# TinyOne.net
KiCad netlist of a schematic drawn in EAGLE
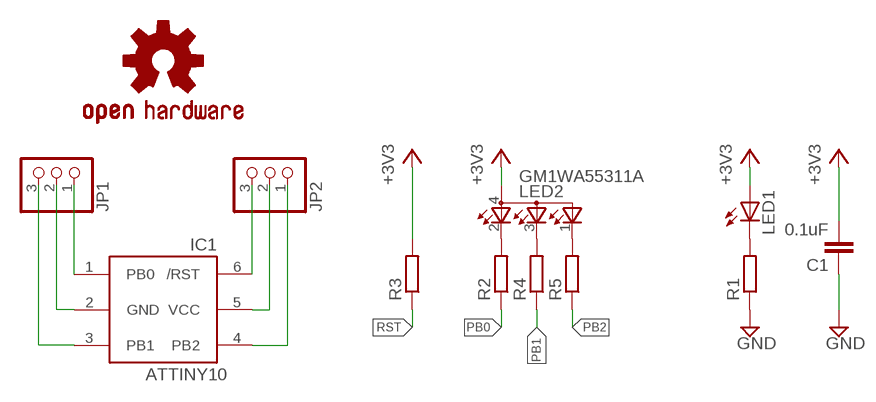
[diagram p0: schematic, sheet 1]

(export (version "E")
  (design (tool "Eeschema 10.0.6"))
  (components
    (comp (ref "C1")
      (value "0.1uF")
      (footprint "eagle-import:C0603")
      (libsource (lib "eagle-import") (part "C-EUC0603"))
    )
    (comp (ref "IC1")
      (value "ATTINY10")
      (footprint "eagle-import:SOT23-6")
      (libsource (lib "eagle-import") (part "ATTINY10"))
    )
    (comp (ref "JP1")
      (value "PINHD-1X3CB")
      (footprint "eagle-import:1X03-CLEANBIG")
      (libsource (lib "eagle-import") (part "PINHD-1X3CB"))
    )
    (comp (ref "JP2")
      (value "PINHD-1X3CB")
      (footprint "eagle-import:1X03-CLEANBIG")
      (libsource (lib "eagle-import") (part "PINHD-1X3CB"))
    )
    (comp (ref "LED1")
      (value "LEDCHIP-LED0603")
      (footprint "eagle-import:CHIP-LED0603")
      (libsource (lib "eagle-import") (part "LEDCHIP-LED0603"))
    )
    (comp (ref "LED2")
      (value "GM1WA55311A")
      (footprint "eagle-import:GM1WA55311A")
      (libsource (lib "eagle-import") (part "GM1WA55311A"))
    )
    (comp (ref "R1")
      (value "R-EU_R0603")
      (footprint "eagle-import:R0603")
      (libsource (lib "eagle-import") (part "R-EU_R0603"))
    )
    (comp (ref "R2")
      (value "R-EU_R0603")
      (footprint "eagle-import:R0603")
      (libsource (lib "eagle-import") (part "R-EU_R0603"))
    )
    (comp (ref "R3")
      (value "R-EU_R0603")
      (footprint "eagle-import:R0603")
      (libsource (lib "eagle-import") (part "R-EU_R0603"))
    )
    (comp (ref "R4")
      (value "R-EU_R0603")
      (footprint "eagle-import:R0603")
      (libsource (lib "eagle-import") (part "R-EU_R0603"))
    )
    (comp (ref "R5")
      (value "R-EU_R0603")
      (footprint "eagle-import:R0603")
      (libsource (lib "eagle-import") (part "R-EU_R0603"))
    )
    (comp (ref "U$1")
      (value "OSHW-LOGOS")
      (footprint "eagle-import:OSHW-LOGO-S")
      (libsource (lib "eagle-import") (part "OSHW-LOGOS"))
    )
  )
  (nets
    (net (code "1") (name "+3V3") (class "Default")
      (node (ref "C1") (pin "2") (pinfunction "2_2") (pintype "passive"))
      (node (ref "IC1") (pin "5") (pinfunction "VCC_5") (pintype "power_in"))
      (node (ref "JP2") (pin "2") (pinfunction "2_2") (pintype "passive"))
      (node (ref "LED1") (pin "A") (pinfunction "A_A") (pintype "passive"))
      (node (ref "LED2") (pin "4") (pinfunction "A_4") (pintype "passive"))
      (node (ref "R3") (pin "2") (pinfunction "2_2") (pintype "passive"))
    )
    (net (code "2") (name "GND") (class "Default")
      (node (ref "C1") (pin "1") (pinfunction "1_1") (pintype "passive"))
      (node (ref "IC1") (pin "2") (pinfunction "GND_2") (pintype "power_in"))
      (node (ref "JP1") (pin "2") (pinfunction "2_2") (pintype "passive"))
      (node (ref "R1") (pin "1") (pinfunction "1_1") (pintype "passive"))
    )
    (net (code "3") (name "Net-(LED1-PadC)") (class "Default")
      (node (ref "LED1") (pin "C") (pinfunction "C_C") (pintype "passive"))
      (node (ref "R1") (pin "2") (pinfunction "2_2") (pintype "passive"))
    )
    (net (code "4") (name "Net-(LED2-CBLUE)") (class "Default")
      (node (ref "LED2") (pin "3") (pinfunction "CBLUE_3") (pintype "passive"))
      (node (ref "R4") (pin "2") (pinfunction "2_2") (pintype "passive"))
    )
    (net (code "5") (name "Net-(LED2-CGREEN)") (class "Default")
      (node (ref "LED2") (pin "1") (pinfunction "CGREEN_1") (pintype "passive"))
      (node (ref "R5") (pin "2") (pinfunction "2_2") (pintype "passive"))
    )
    (net (code "6") (name "Net-(LED2-CRED)") (class "Default")
      (node (ref "LED2") (pin "2") (pinfunction "CRED_2") (pintype "passive"))
      (node (ref "R2") (pin "2") (pinfunction "2_2") (pintype "passive"))
    )
    (net (code "7") (name "PB0") (class "Default")
      (node (ref "IC1") (pin "1") (pinfunction "PB0_1") (pintype "bidirectional"))
      (node (ref "JP1") (pin "1") (pinfunction "1_1") (pintype "passive"))
      (node (ref "R2") (pin "1") (pinfunction "1_1") (pintype "passive"))
    )
    (net (code "8") (name "PB1") (class "Default")
      (node (ref "IC1") (pin "3") (pinfunction "PB1_3") (pintype "bidirectional"))
      (node (ref "JP1") (pin "3") (pinfunction "3_3") (pintype "passive"))
      (node (ref "R4") (pin "1") (pinfunction "1_1") (pintype "passive"))
    )
    (net (code "9") (name "PB2") (class "Default")
      (node (ref "IC1") (pin "4") (pinfunction "PB2_4") (pintype "bidirectional"))
      (node (ref "JP2") (pin "1") (pinfunction "1_1") (pintype "passive"))
      (node (ref "R5") (pin "1") (pinfunction "1_1") (pintype "passive"))
    )
    (net (code "10") (name "RST") (class "Default")
      (node (ref "IC1") (pin "6") (pinfunction "/RST_6") (pintype "bidirectional"))
      (node (ref "JP2") (pin "3") (pinfunction "3_3") (pintype "passive"))
      (node (ref "R3") (pin "1") (pinfunction "1_1") (pintype "passive"))
    )
  )
)
